# Test_and_Fiducials.net
KiCad netlist of a schematic drawn in Altium Designer
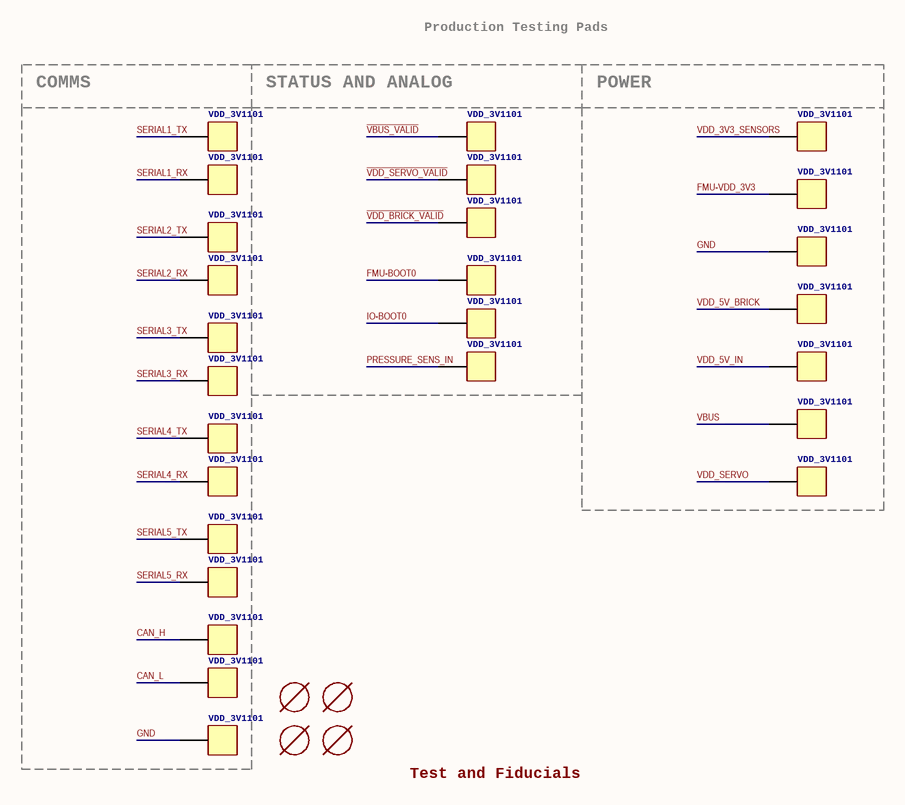
[diagram p0: Test and Fiducials.SchDoc]

(export (version "E")
  (design (tool "Eeschema 10.0.6"))
  (components
    (comp (ref "!VBUS_VALID")
      (value "PAD.04")
      (footprint "PAD.04X.04")
      (fields (field (name ">NAME") "VDD_3V1101"))
      (libsource (lib "PX4") (part "PAD.04"))
    )
    (comp (ref "!VDD_BRICK_VALID")
      (value "PAD.04")
      (footprint "PAD.04X.04")
      (fields (field (name ">NAME") "VDD_3V1101"))
      (libsource (lib "PX4") (part "PAD.04"))
    )
    (comp (ref "!VDD_SERVO_VALID")
      (value "PAD.04")
      (footprint "PAD.04X.04")
      (fields (field (name ">NAME") "VDD_3V1101"))
      (libsource (lib "PX4") (part "PAD.04"))
    )
    (comp (ref "ADC_PR")
      (value "PAD.04")
      (footprint "PAD.04X.04")
      (fields (field (name ">NAME") "VDD_3V1101"))
      (libsource (lib "PX4") (part "PAD.04"))
    )
    (comp (ref "CAN_H")
      (value "PAD.04")
      (footprint "PAD.04X.04")
      (fields (field (name ">NAME") "VDD_3V1101"))
      (libsource (lib "PX4") (part "PAD.04"))
    )
    (comp (ref "CAN_L")
      (value "PAD.04")
      (footprint "PAD.04X.04")
      (fields (field (name ">NAME") "VDD_3V1101"))
      (libsource (lib "PX4") (part "PAD.04"))
    )
    (comp (ref "FMU-BOOT1101")
      (value "PAD.04")
      (footprint "PAD.04X.04")
      (fields (field (name ">NAME") "VDD_3V1101"))
      (libsource (lib "PX4") (part "PAD.04"))
    )
    (comp (ref "GND")
      (value "PAD.04")
      (footprint "PAD.04X.04")
      (fields (field (name ">NAME") "VDD_3V1101"))
      (libsource (lib "PX4") (part "PAD.04"))
    )
    (comp (ref "GND.")
      (value "PAD.04")
      (footprint "PAD.04X.04")
      (fields (field (name ">NAME") "VDD_3V1101"))
      (libsource (lib "PX4") (part "PAD.04"))
    )
    (comp (ref "IO-BOOT1101")
      (value "PAD.04")
      (footprint "PAD.04X.04")
      (fields (field (name ">NAME") "VDD_3V1101"))
      (libsource (lib "PX4") (part "PAD.04"))
    )
    (comp (ref "M3_MOUNT1101")
      (value "MOUNT-HOLE3.1MM")
      (footprint "MOUNT-HOLE3.1")
      (libsource (lib "pixhawk2") (part "MOUNT-HOLE3.1MM"))
    )
    (comp (ref "M3_MOUNT1102")
      (value "MOUNT-HOLE3.1MM")
      (footprint "MOUNT-HOLE3.1")
      (libsource (lib "pixhawk2") (part "MOUNT-HOLE3.1MM"))
    )
    (comp (ref "M3_MOUNT1103")
      (value "MOUNT-HOLE3.1MM")
      (footprint "MOUNT-HOLE3.1")
      (libsource (lib "pixhawk2") (part "MOUNT-HOLE3.1MM"))
    )
    (comp (ref "M3_MOUNT1104")
      (value "MOUNT-HOLE3.1MM")
      (footprint "MOUNT-HOLE3.1")
      (libsource (lib "pixhawk2") (part "MOUNT-HOLE3.1MM"))
    )
    (comp (ref "S1RX")
      (value "PAD.04")
      (footprint "PAD.04X.04")
      (fields (field (name ">NAME") "VDD_3V1101"))
      (libsource (lib "PX4") (part "PAD.04"))
    )
    (comp (ref "S1TX")
      (value "PAD.04")
      (footprint "PAD.04X.04")
      (fields (field (name ">NAME") "VDD_3V1101"))
      (libsource (lib "PX4") (part "PAD.04"))
    )
    (comp (ref "S2RX")
      (value "PAD.04")
      (footprint "PAD.04X.04")
      (fields (field (name ">NAME") "VDD_3V1101"))
      (libsource (lib "PX4") (part "PAD.04"))
    )
    (comp (ref "S2TX")
      (value "PAD.04")
      (footprint "PAD.04X.04")
      (fields (field (name ">NAME") "VDD_3V1101"))
      (libsource (lib "PX4") (part "PAD.04"))
    )
    (comp (ref "S3RX")
      (value "PAD.04")
      (footprint "PAD.04X.04")
      (fields (field (name ">NAME") "VDD_3V1101"))
      (libsource (lib "PX4") (part "PAD.04"))
    )
    (comp (ref "S3TX")
      (value "PAD.04")
      (footprint "PAD.04X.04")
      (fields (field (name ">NAME") "VDD_3V1101"))
      (libsource (lib "PX4") (part "PAD.04"))
    )
    (comp (ref "S4RX")
      (value "PAD.04")
      (footprint "PAD.04X.04")
      (fields (field (name ">NAME") "VDD_3V1101"))
      (libsource (lib "PX4") (part "PAD.04"))
    )
    (comp (ref "S4TX")
      (value "PAD.04")
      (footprint "PAD.04X.04")
      (fields (field (name ">NAME") "VDD_3V1101"))
      (libsource (lib "PX4") (part "PAD.04"))
    )
    (comp (ref "S5_RX")
      (value "PAD.04")
      (footprint "PAD.04X.04")
      (fields (field (name ">NAME") "VDD_3V1101"))
      (libsource (lib "PX4") (part "PAD.04"))
    )
    (comp (ref "S5_TX")
      (value "PAD.04")
      (footprint "PAD.04X.04")
      (fields (field (name ">NAME") "VDD_3V1101"))
      (libsource (lib "PX4") (part "PAD.04"))
    )
    (comp (ref "VBUS")
      (value "PAD.04")
      (footprint "PAD.04X.04")
      (fields (field (name ">NAME") "VDD_3V1101"))
      (libsource (lib "PX4") (part "PAD.04"))
    )
    (comp (ref "VDDA_3V1101")
      (value "PAD.04")
      (footprint "PAD.04X.04")
      (fields (field (name ">NAME") "VDD_3V1101"))
      (libsource (lib "PX4") (part "PAD.04"))
    )
    (comp (ref "VDD_3V1101")
      (value "PAD.04")
      (footprint "PAD.04X.04")
      (fields (field (name ">NAME") "VDD_3V1101"))
      (libsource (lib "PX4") (part "PAD.04"))
    )
    (comp (ref "VDD_5V_BRICK")
      (value "PAD.04")
      (footprint "PAD.04X.04")
      (fields (field (name ">NAME") "VDD_3V1101"))
      (libsource (lib "PX4") (part "PAD.04"))
    )
    (comp (ref "VDD_5V_IN")
      (value "PAD.04")
      (footprint "PAD.04X.04")
      (fields (field (name ">NAME") "VDD_3V1101"))
      (libsource (lib "PX4") (part "PAD.04"))
    )
    (comp (ref "VDD_SERVO")
      (value "PAD.04")
      (footprint "PAD.04X.04")
      (fields (field (name ">NAME") "VDD_3V1101"))
      (libsource (lib "PX4") (part "PAD.04"))
    )
  )
  (nets
    (net (code "1") (name "/CAN_H") (class "Default")
      (node (ref "CAN_H") (pin "P$1") (pinfunction "P$1_P$1") (pintype "passive"))
    )
    (net (code "2") (name "/CAN_L") (class "Default")
      (node (ref "CAN_L") (pin "P$1") (pinfunction "P$1_P$1") (pintype "passive"))
    )
    (net (code "3") (name "/FMU-BOOT0") (class "Default")
      (node (ref "FMU-BOOT1101") (pin "P$1") (pinfunction "P$1_P$1") (pintype "passive"))
    )
    (net (code "4") (name "/FMU-VDD_3V3") (class "Default")
      (node (ref "VDD_3V1101") (pin "P$1") (pinfunction "P$1_P$1") (pintype "passive"))
    )
    (net (code "5") (name "/GND") (class "Default")
      (node (ref "GND") (pin "P$1") (pinfunction "P$1_P$1") (pintype "passive"))
      (node (ref "GND.") (pin "P$1") (pinfunction "P$1_P$1") (pintype "passive"))
    )
    (net (code "6") (name "/IO-BOOT0") (class "Default")
      (node (ref "IO-BOOT1101") (pin "P$1") (pinfunction "P$1_P$1") (pintype "passive"))
    )
    (net (code "7") (name "/PRESSURE_SENS_IN") (class "Default")
      (node (ref "ADC_PR") (pin "P$1") (pinfunction "P$1_P$1") (pintype "passive"))
    )
    (net (code "8") (name "/SERIAL1_RX") (class "Default")
      (node (ref "S1RX") (pin "P$1") (pinfunction "P$1_P$1") (pintype "passive"))
    )
    (net (code "9") (name "/SERIAL1_TX") (class "Default")
      (node (ref "S1TX") (pin "P$1") (pinfunction "P$1_P$1") (pintype "passive"))
    )
    (net (code "10") (name "/SERIAL2_RX") (class "Default")
      (node (ref "S2RX") (pin "P$1") (pinfunction "P$1_P$1") (pintype "passive"))
    )
    (net (code "11") (name "/SERIAL2_TX") (class "Default")
      (node (ref "S2TX") (pin "P$1") (pinfunction "P$1_P$1") (pintype "passive"))
    )
    (net (code "12") (name "/SERIAL3_RX") (class "Default")
      (node (ref "S3RX") (pin "P$1") (pinfunction "P$1_P$1") (pintype "passive"))
    )
    (net (code "13") (name "/SERIAL3_TX") (class "Default")
      (node (ref "S3TX") (pin "P$1") (pinfunction "P$1_P$1") (pintype "passive"))
    )
    (net (code "14") (name "/SERIAL4_RX") (class "Default")
      (node (ref "S4RX") (pin "P$1") (pinfunction "P$1_P$1") (pintype "passive"))
    )
    (net (code "15") (name "/SERIAL4_TX") (class "Default")
      (node (ref "S4TX") (pin "P$1") (pinfunction "P$1_P$1") (pintype "passive"))
    )
    (net (code "16") (name "/SERIAL5_RX") (class "Default")
      (node (ref "S5_RX") (pin "P$1") (pinfunction "P$1_P$1") (pintype "passive"))
    )
    (net (code "17") (name "/SERIAL5_TX") (class "Default")
      (node (ref "S5_TX") (pin "P$1") (pinfunction "P$1_P$1") (pintype "passive"))
    )
    (net (code "18") (name "/VBUS") (class "Default")
      (node (ref "VBUS") (pin "P$1") (pinfunction "P$1_P$1") (pintype "passive"))
    )
    (net (code "19") (name "/VDD_3V3_SENSORS") (class "Default")
      (node (ref "VDDA_3V1101") (pin "P$1") (pinfunction "P$1_P$1") (pintype "passive"))
    )
    (net (code "20") (name "/VDD_5V_BRICK") (class "Default")
      (node (ref "VDD_5V_BRICK") (pin "P$1") (pinfunction "P$1_P$1") (pintype "passive"))
    )
    (net (code "21") (name "/VDD_5V_IN") (class "Default")
      (node (ref "VDD_5V_IN") (pin "P$1") (pinfunction "P$1_P$1") (pintype "passive"))
    )
    (net (code "22") (name "/VDD_SERVO") (class "Default")
      (node (ref "VDD_SERVO") (pin "P$1") (pinfunction "P$1_P$1") (pintype "passive"))
    )
    (net (code "23") (name "/~{VBUS_VALID}") (class "Default")
      (node (ref "!VBUS_VALID") (pin "P$1") (pinfunction "P$1_P$1") (pintype "passive"))
    )
    (net (code "24") (name "/~{VDD_BRICK_VALID}") (class "Default")
      (node (ref "!VDD_BRICK_VALID") (pin "P$1") (pinfunction "P$1_P$1") (pintype "passive"))
    )
    (net (code "25") (name "/~{VDD_SERVO_VALID}") (class "Default")
      (node (ref "!VDD_SERVO_VALID") (pin "P$1") (pinfunction "P$1_P$1") (pintype "passive"))
    )
  )
)
